# weightScale.net
KiCad netlist of a schematic drawn in EAGLE
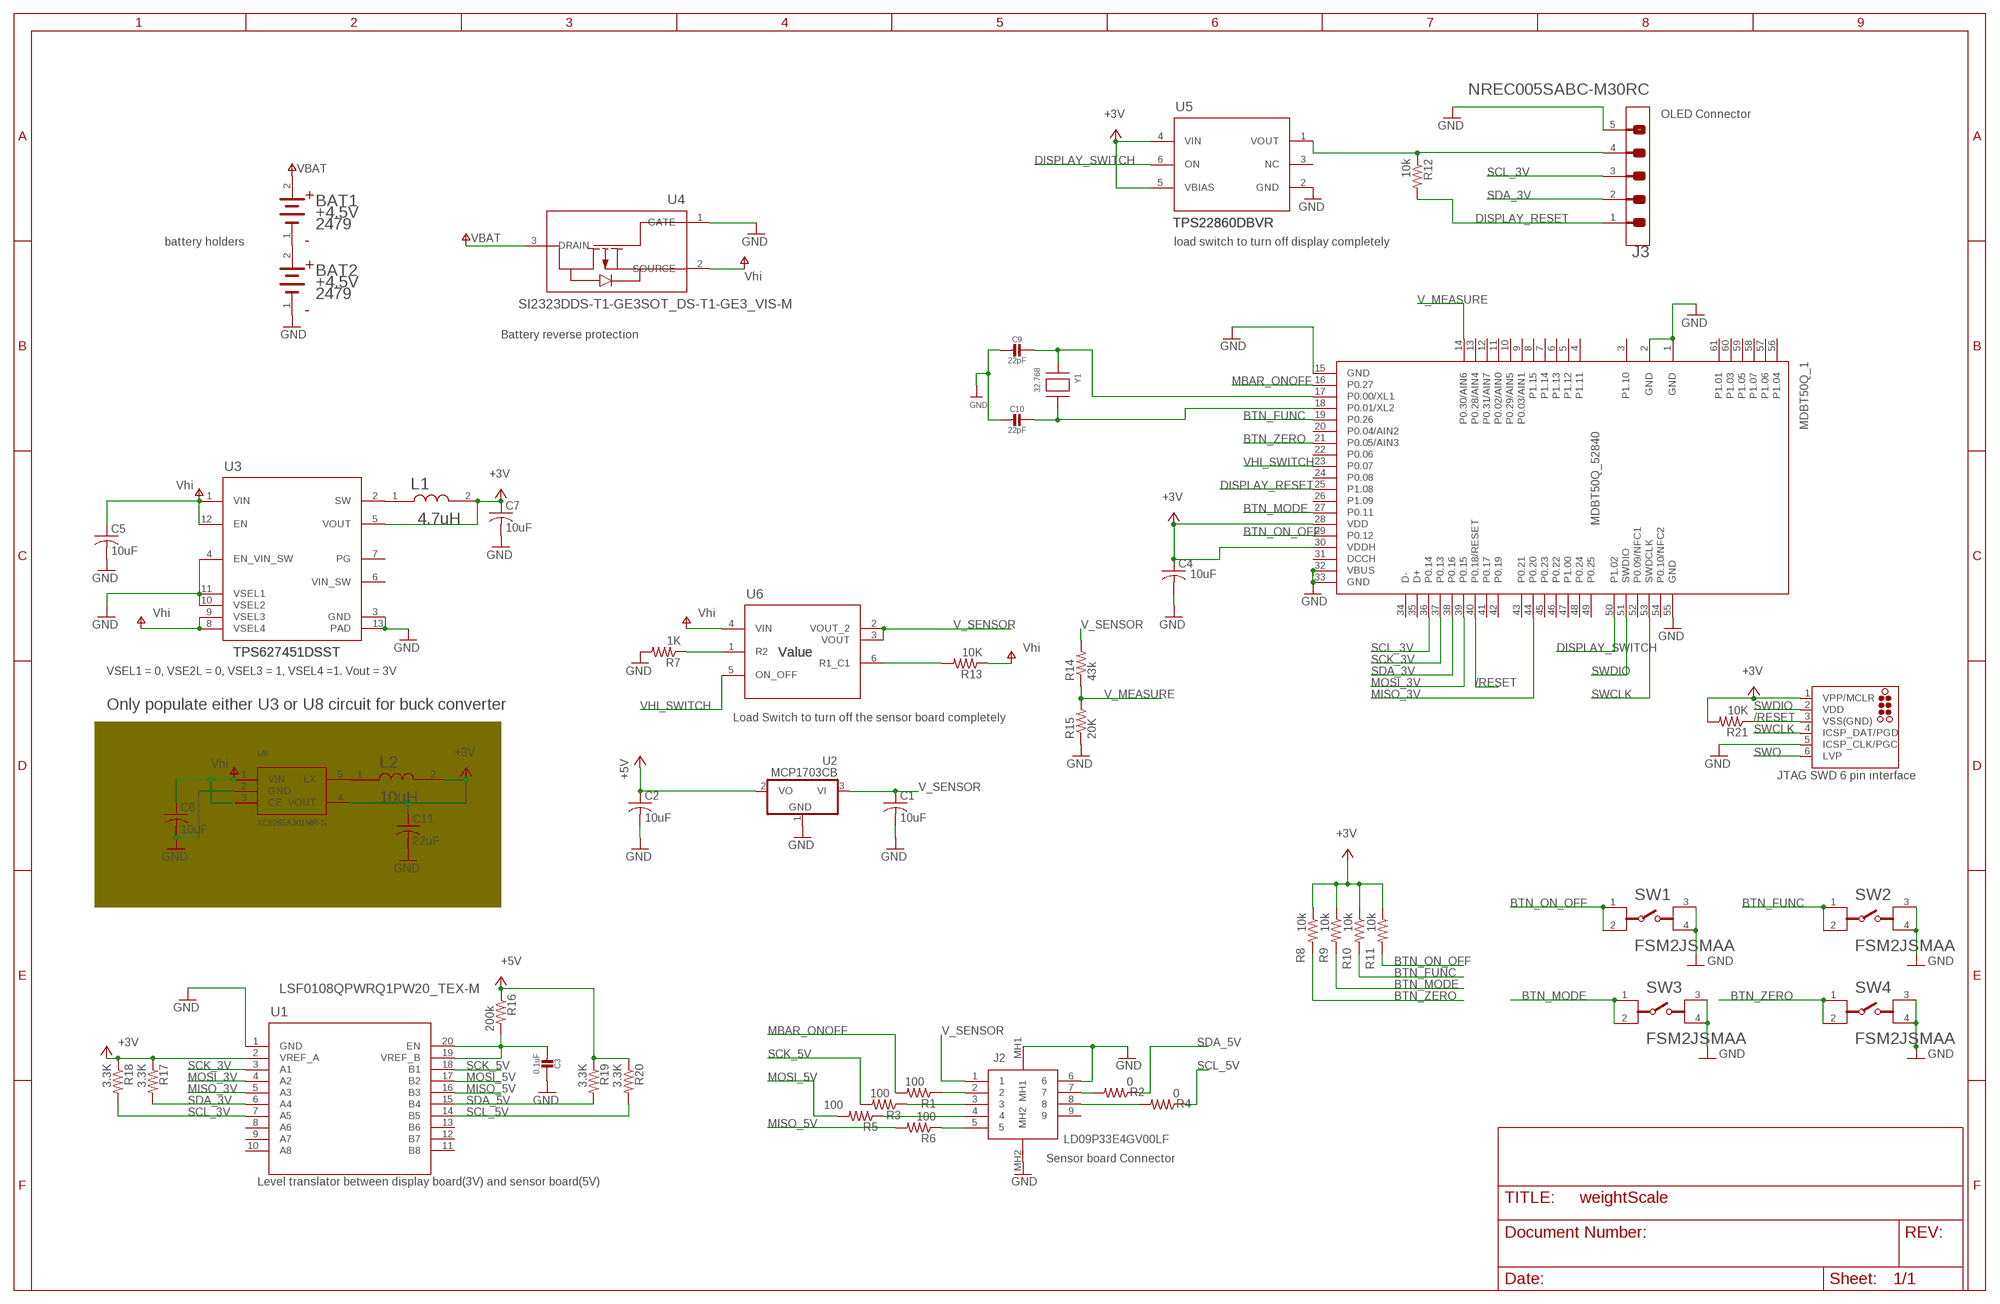
[diagram p0: schematic, sheet 1]

(export (version "E")
  (design (tool "Eeschema 10.0.6"))
  (components
    (comp (ref "BAT1")
      (value "KEYSTONE_2479KEYSTONE_2479_0_0")
      (footprint "eagle-import:KEYSTONE_2479_0")
      (fields
        (field (name "DIGIKEY_PART_NUMBER") "36-2479-ND")
        (field (name "MF") "Keystone")
        (field (name "MOUSER_PART_NUMBER") "534-2479")
      )
      (libsource (lib "eagle-import") (part "KEYSTONE_2479KEYSTONE_2479_0_0"))
    )
    (comp (ref "BAT2")
      (value "KEYSTONE_2479KEYSTONE_2479_0_0")
      (footprint "eagle-import:KEYSTONE_2479_0")
      (fields
        (field (name "DIGIKEY_PART_NUMBER") "36-2479-ND")
        (field (name "MF") "Keystone")
        (field (name "MOUSER_PART_NUMBER") "534-2479")
      )
      (libsource (lib "eagle-import") (part "KEYSTONE_2479KEYSTONE_2479_0_0"))
    )
    (comp (ref "C1")
      (value "10uF")
      (footprint "eagle-import:C0805")
      (libsource (lib "eagle-import") (part "C-USC0805"))
    )
    (comp (ref "C2")
      (value "10uF")
      (footprint "eagle-import:C0805")
      (libsource (lib "eagle-import") (part "C-USC0805"))
    )
    (comp (ref "C3")
      (value "0.1uF")
      (footprint "eagle-import:_0603MP")
      (libsource (lib "eagle-import") (part "CAP_CERAMIC_0603MP"))
    )
    (comp (ref "C4")
      (value "10uF")
      (footprint "eagle-import:C1206")
      (libsource (lib "eagle-import") (part "C-USC1206"))
    )
    (comp (ref "C5")
      (value "10uF")
      (footprint "eagle-import:C0805")
      (libsource (lib "eagle-import") (part "C-USC0805"))
    )
    (comp (ref "C6")
      (value "10uF")
      (footprint "eagle-import:C0603K")
      (libsource (lib "eagle-import") (part "C-USC0603K"))
    )
    (comp (ref "C7")
      (value "10uF")
      (footprint "eagle-import:C0805")
      (libsource (lib "eagle-import") (part "C-USC0805"))
    )
    (comp (ref "C9")
      (value "22pF")
      (footprint "eagle-import:_0603MP")
      (libsource (lib "eagle-import") (part "CAP_CERAMIC_0603MP"))
    )
    (comp (ref "C10")
      (value "22pF")
      (footprint "eagle-import:_0603MP")
      (libsource (lib "eagle-import") (part "CAP_CERAMIC_0603MP"))
    )
    (comp (ref "C11")
      (value "22uF")
      (footprint "eagle-import:C0603K")
      (libsource (lib "eagle-import") (part "C-USC0603K"))
    )
    (comp (ref "J2")
      (value "LD09P33E4GV00LF")
      (footprint "eagle-import:LD09P33E4GV00LF")
      (fields (field (name "MOUSER_PART_NUMBER") "649-LD09P33E4GV00LF"))
      (libsource (lib "eagle-import") (part "LD09P33E4GV00LF"))
    )
    (comp (ref "J3")
      (value "SULLINS_NREC005SABC-M30RCSULLINS_NREC005SABC-M30RC_0_0")
      (footprint "eagle-import:SULLINS_NREC005SABC-M30RC_0")
      (fields
        (field (name "DIGIKEY_PART_NUMBER") "CONN HEADER .100\" SNGL SMD 5POS")
        (field (name "MF") "Sullins")
        (field (name "MPN") "NREC005SABC-M30RC")
      )
      (libsource (lib "eagle-import") (part "SULLINS_NREC005SABC-M30RCSULLINS_NREC005SABC-M30RC_0_0"))
    )
    (comp (ref "J4")
      (value "TC2030-MCP-NL")
      (footprint "eagle-import:TC2030-MCP-NL")
      (libsource (lib "eagle-import") (part "TC2030-MCP-NL"))
    )
    (comp (ref "L1")
      (value "MURATA_DFE252010F-4R7M=P2MURATA_DFE252010F-4R7M=P2_0_0")
      (footprint "eagle-import:MURATA_DFE252010F-4R7M=P2_0")
      (fields
        (field (name "MF") "Murata")
        (field (name "MPN") "DFE252010F-4R7M=P2")
        (field (name "TOLERANCE") "0.2")
      )
      (libsource (lib "eagle-import") (part "MURATA_DFE252010F-4R7M=P2MURATA_DFE252010F-4R7M=P2_0_0"))
    )
    (comp (ref "L2")
      (value "MURATA_1239AS-H-100M=P2MURATA_1239AS-H-100M=P2_0_0")
      (footprint "eagle-import:MURATA_1239AS-H-100M=P2_0")
      (fields
        (field (name "DIGIKEY_PART_NUMBER") "490-10563-1-ND")
        (field (name "MF") "Murata")
        (field (name "MOUSER_PART_NUMBER") "81-1239AS-H-100MP2")
      )
      (libsource (lib "eagle-import") (part "MURATA_1239AS-H-100M=P2MURATA_1239AS-H-100M=P2_0_0"))
    )
    (comp (ref "MDBT50Q_1")
      (value "MDBT50Q_52840")
      (footprint "eagle-import:MDBT50Q")
      (libsource (lib "eagle-import") (part "MDBT50Q_52840"))
    )
    (comp (ref "R1")
      (value "100")
      (footprint "eagle-import:R0603")
      (libsource (lib "eagle-import") (part "R-US_R0603"))
    )
    (comp (ref "R2")
      (value "0")
      (footprint "eagle-import:R0603")
      (libsource (lib "eagle-import") (part "R-US_R0603"))
    )
    (comp (ref "R3")
      (value "100")
      (footprint "eagle-import:R0603")
      (libsource (lib "eagle-import") (part "R-US_R0603"))
    )
    (comp (ref "R4")
      (value "0")
      (footprint "eagle-import:R0603")
      (libsource (lib "eagle-import") (part "R-US_R0603"))
    )
    (comp (ref "R5")
      (value "100")
      (footprint "eagle-import:R0603")
      (libsource (lib "eagle-import") (part "R-US_R0603"))
    )
    (comp (ref "R6")
      (value "100")
      (footprint "eagle-import:R0603")
      (libsource (lib "eagle-import") (part "R-US_R0603"))
    )
    (comp (ref "R7")
      (value "1K")
      (footprint "eagle-import:R0603")
      (libsource (lib "eagle-import") (part "R-US_R0603"))
    )
    (comp (ref "R8")
      (value "10k")
      (footprint "eagle-import:R0603")
      (libsource (lib "eagle-import") (part "R-US_R0603"))
    )
    (comp (ref "R9")
      (value "10k")
      (footprint "eagle-import:R0603")
      (libsource (lib "eagle-import") (part "R-US_R0603"))
    )
    (comp (ref "R10")
      (value "10k")
      (footprint "eagle-import:R0603")
      (libsource (lib "eagle-import") (part "R-US_R0603"))
    )
    (comp (ref "R11")
      (value "10k")
      (footprint "eagle-import:R0603")
      (libsource (lib "eagle-import") (part "R-US_R0603"))
    )
    (comp (ref "R12")
      (value "10k")
      (footprint "eagle-import:R0603")
      (libsource (lib "eagle-import") (part "R-US_R0603"))
    )
    (comp (ref "R13")
      (value "10K")
      (footprint "eagle-import:R0603")
      (libsource (lib "eagle-import") (part "R-US_R0603"))
    )
    (comp (ref "R14")
      (value "43k")
      (footprint "eagle-import:R0603")
      (libsource (lib "eagle-import") (part "R-US_R0603"))
    )
    (comp (ref "R15")
      (value "20K")
      (footprint "eagle-import:R0603")
      (libsource (lib "eagle-import") (part "R-US_R0603"))
    )
    (comp (ref "R16")
      (value "200k")
      (footprint "eagle-import:R0603")
      (libsource (lib "eagle-import") (part "R-US_R0603"))
    )
    (comp (ref "R17")
      (value "3.3K")
      (footprint "eagle-import:R0603")
      (libsource (lib "eagle-import") (part "R-US_R0603"))
    )
    (comp (ref "R18")
      (value "3.3K")
      (footprint "eagle-import:R0603")
      (libsource (lib "eagle-import") (part "R-US_R0603"))
    )
    (comp (ref "R19")
      (value "3.3K")
      (footprint "eagle-import:R0603")
      (libsource (lib "eagle-import") (part "R-US_R0603"))
    )
    (comp (ref "R20")
      (value "3.3K")
      (footprint "eagle-import:R0603")
      (libsource (lib "eagle-import") (part "R-US_R0603"))
    )
    (comp (ref "R21")
      (value "10K")
      (footprint "eagle-import:R0603")
      (libsource (lib "eagle-import") (part "R-US_R0603"))
    )
    (comp (ref "SW1")
      (value "TE_CONNECTIVITY_FSM2JSMAATE_CONNECTIVITY_FSM2JSMAA_0_0")
      (footprint "eagle-import:TE_CONNECTIVITY_FSM2JSMAA_0")
      (fields
        (field (name "DIGIKEY_PART_NUMBER") "450-3355-ND")
        (field (name "MF") "TE Connectivity")
        (field (name "MOUSER_PART_NUMBER") "506-2-1437565-8")
      )
      (libsource (lib "eagle-import") (part "TE_CONNECTIVITY_FSM2JSMAATE_CONNECTIVITY_FSM2JSMAA_0_0"))
    )
    (comp (ref "SW2")
      (value "TE_CONNECTIVITY_FSM2JSMAATE_CONNECTIVITY_FSM2JSMAA_0_0")
      (footprint "eagle-import:TE_CONNECTIVITY_FSM2JSMAA_0")
      (fields
        (field (name "DIGIKEY_PART_NUMBER") "450-3355-ND")
        (field (name "MF") "TE Connectivity")
        (field (name "MOUSER_PART_NUMBER") "506-2-1437565-8")
      )
      (libsource (lib "eagle-import") (part "TE_CONNECTIVITY_FSM2JSMAATE_CONNECTIVITY_FSM2JSMAA_0_0"))
    )
    (comp (ref "SW3")
      (value "TE_CONNECTIVITY_FSM2JSMAATE_CONNECTIVITY_FSM2JSMAA_0_0")
      (footprint "eagle-import:TE_CONNECTIVITY_FSM2JSMAA_0")
      (fields
        (field (name "DIGIKEY_PART_NUMBER") "450-3355-ND")
        (field (name "MF") "TE Connectivity")
        (field (name "MOUSER_PART_NUMBER") "506-2-1437565-8")
      )
      (libsource (lib "eagle-import") (part "TE_CONNECTIVITY_FSM2JSMAATE_CONNECTIVITY_FSM2JSMAA_0_0"))
    )
    (comp (ref "SW4")
      (value "TE_CONNECTIVITY_FSM2JSMAATE_CONNECTIVITY_FSM2JSMAA_0_0")
      (footprint "eagle-import:TE_CONNECTIVITY_FSM2JSMAA_0")
      (fields
        (field (name "DIGIKEY_PART_NUMBER") "450-3355-ND")
        (field (name "MF") "TE Connectivity")
        (field (name "MOUSER_PART_NUMBER") "506-2-1437565-8")
      )
      (libsource (lib "eagle-import") (part "TE_CONNECTIVITY_FSM2JSMAATE_CONNECTIVITY_FSM2JSMAA_0_0"))
    )
    (comp (ref "U1")
      (value "LSF0108QPWRQ1PW20_TEX-M")
      (footprint "eagle-import:PW20_TEX-M")
      (fields
        (field (name "MANUFACTURER_PART_NUMBER") "LSF0108QPWRQ1")
        (field (name "COPYRIGHT") "Copyright (C) 2021 Ultra Librarian. All rights reserved.")
      )
      (libsource (lib "eagle-import") (part "LSF0108QPWRQ1PW20_TEX-M"))
    )
    (comp (ref "U2")
      (value "MCP1703CB")
      (footprint "eagle-import:SOT23")
      (libsource (lib "eagle-import") (part "MCP1703CB"))
    )
    (comp (ref "U3")
      (value "TPS627451DSST")
      (footprint "eagle-import:DSS0012A")
      (fields (field (name "COPYRIGHT") "Copyright (C) 2021 Ultra Librarian. All rights reserved."))
      (libsource (lib "eagle-import") (part "TPS627451DSST"))
    )
    (comp (ref "U4")
      (value "SI2323DDS-T1-GE3SOT_DS-T1-GE3_VIS-M")
      (footprint "eagle-import:SOT_DS-T1-GE3_VIS-M")
      (fields
        (field (name "MANUFACTURER_PART_NUMBER") "SI2323DDS-T1-GE3")
        (field (name "COPYRIGHT") "Copyright (C) 2021 Ultra Librarian. All rights reserved.")
      )
      (libsource (lib "eagle-import") (part "SI2323DDS-T1-GE3SOT_DS-T1-GE3_VIS-M"))
    )
    (comp (ref "U5")
      (value "TPS22860DBVR")
      (footprint "eagle-import:DBV0006A_N")
      (fields (field (name "COPYRIGHT") "Copyright (C) 2021 Ultra Librarian. All rights reserved."))
      (libsource (lib "eagle-import") (part "TPS22860DBVR"))
    )
    (comp (ref "U6")
      (value "Value")
      (footprint "eagle-import:DDC0006A_N")
      (fields (field (name "MANUFACTURER") "Texas Instruments") (field (name "PARTNUMBER") "TPS27081ADDCR"))
      (libsource (lib "eagle-import") (part "TPS27081ADDCR"))
    )
    (comp (ref "U8")
      (value "XC9265A301MR-G")
      (footprint "eagle-import:SOT-25")
      (libsource (lib "eagle-import") (part "XC9265A301MR-G"))
    )
    (comp (ref "Y1")
      (value "32.768")
      (footprint "eagle-import:XTAL3215")
      (libsource (lib "eagle-import") (part "XTAL-3.2X1.5"))
    )
  )
  (nets
    (net (code "1") (name "+3V") (class "Default")
      (node (ref "C11") (pin "1") (pinfunction "1_1") (pintype "passive"))
      (node (ref "C4") (pin "1") (pinfunction "1_1") (pintype "passive"))
      (node (ref "C7") (pin "1") (pinfunction "1_1") (pintype "passive"))
      (node (ref "J4") (pin "1") (pinfunction "VPP/MCLR_1") (pintype "passive"))
      (node (ref "L1") (pin "2") (pinfunction "2_2") (pintype "passive"))
      (node (ref "L2") (pin "2") (pinfunction "2_2") (pintype "passive"))
      (node (ref "MDBT50Q_1") (pin "28") (pinfunction "VDD_28") (pintype "bidirectional"))
      (node (ref "MDBT50Q_1") (pin "30") (pinfunction "VDDH_30") (pintype "bidirectional"))
      (node (ref "R10") (pin "1") (pinfunction "1_1") (pintype "passive"))
      (node (ref "R11") (pin "1") (pinfunction "1_1") (pintype "passive"))
      (node (ref "R17") (pin "1") (pinfunction "1_1") (pintype "passive"))
      (node (ref "R18") (pin "1") (pinfunction "1_1") (pintype "passive"))
      (node (ref "R21") (pin "2") (pinfunction "2_2") (pintype "passive"))
      (node (ref "R8") (pin "1") (pinfunction "1_1") (pintype "passive"))
      (node (ref "R9") (pin "1") (pinfunction "1_1") (pintype "passive"))
      (node (ref "U1") (pin "2") (pinfunction "VREF_A_2") (pintype "passive"))
      (node (ref "U3") (pin "5") (pinfunction "VOUT_5") (pintype "input"))
      (node (ref "U5") (pin "4") (pinfunction "VIN_4") (pintype "power_in"))
      (node (ref "U5") (pin "5") (pinfunction "VBIAS_5") (pintype "input"))
      (node (ref "U8") (pin "4") (pinfunction "VOUT_4") (pintype "bidirectional"))
    )
    (net (code "2") (name "+5V") (class "Default")
      (node (ref "C2") (pin "1") (pinfunction "1_1") (pintype "passive"))
      (node (ref "R16") (pin "1") (pinfunction "1_1") (pintype "passive"))
      (node (ref "R19") (pin "1") (pinfunction "1_1") (pintype "passive"))
      (node (ref "R20") (pin "1") (pinfunction "1_1") (pintype "passive"))
      (node (ref "U2") (pin "2") (pinfunction "VO_2") (pintype "passive"))
    )
    (net (code "3") (name "/BTN_FUNC") (class "Default")
      (node (ref "MDBT50Q_1") (pin "19") (pinfunction "P0.26_19") (pintype "bidirectional"))
      (node (ref "R10") (pin "2") (pinfunction "2_2") (pintype "passive"))
      (node (ref "SW2") (pin "1") (pinfunction "1_1") (pintype "passive"))
      (node (ref "SW2") (pin "2") (pinfunction "2_2") (pintype "passive"))
    )
    (net (code "4") (name "/BTN_MODE") (class "Default")
      (node (ref "MDBT50Q_1") (pin "27") (pinfunction "P0.11_27") (pintype "bidirectional"))
      (node (ref "R9") (pin "2") (pinfunction "2_2") (pintype "passive"))
      (node (ref "SW3") (pin "1") (pinfunction "1_1") (pintype "passive"))
      (node (ref "SW3") (pin "2") (pinfunction "2_2") (pintype "passive"))
    )
    (net (code "5") (name "/BTN_ON_OFF") (class "Default")
      (node (ref "MDBT50Q_1") (pin "29") (pinfunction "P0.12_29") (pintype "bidirectional"))
      (node (ref "R11") (pin "2") (pinfunction "2_2") (pintype "passive"))
      (node (ref "SW1") (pin "1") (pinfunction "1_1") (pintype "passive"))
      (node (ref "SW1") (pin "2") (pinfunction "2_2") (pintype "passive"))
    )
    (net (code "6") (name "/BTN_ZERO") (class "Default")
      (node (ref "MDBT50Q_1") (pin "21") (pinfunction "P0.05/AIN3_21") (pintype "bidirectional"))
      (node (ref "R8") (pin "2") (pinfunction "2_2") (pintype "passive"))
      (node (ref "SW4") (pin "1") (pinfunction "1_1") (pintype "passive"))
      (node (ref "SW4") (pin "2") (pinfunction "2_2") (pintype "passive"))
    )
    (net (code "7") (name "/DISPLAY_RESET") (class "Default")
      (node (ref "J3") (pin "1") (pinfunction "1_1") (pintype "bidirectional"))
      (node (ref "MDBT50Q_1") (pin "25") (pinfunction "P1.08_25") (pintype "bidirectional"))
      (node (ref "R12") (pin "2") (pinfunction "2_2") (pintype "passive"))
    )
    (net (code "8") (name "/DISPLAY_SWITCH") (class "Default")
      (node (ref "MDBT50Q_1") (pin "50") (pinfunction "P1.02_50") (pintype "bidirectional"))
      (node (ref "U5") (pin "6") (pinfunction "ON_6") (pintype "input"))
    )
    (net (code "9") (name "/MBAR_ONOFF") (class "Default")
      (node (ref "MDBT50Q_1") (pin "16") (pinfunction "P0.27_16") (pintype "bidirectional"))
      (node (ref "R1") (pin "2") (pinfunction "2_2") (pintype "passive"))
    )
    (net (code "10") (name "/MISO_3V") (class "Default")
      (node (ref "MDBT50Q_1") (pin "44") (pinfunction "P0.20_44") (pintype "bidirectional"))
      (node (ref "U1") (pin "5") (pinfunction "A3_5") (pintype "passive"))
    )
    (net (code "11") (name "/MISO_5V") (class "Default")
      (node (ref "R6") (pin "2") (pinfunction "2_2") (pintype "passive"))
      (node (ref "U1") (pin "16") (pinfunction "B3_16") (pintype "passive"))
    )
    (net (code "12") (name "/MOSI_3V") (class "Default")
      (node (ref "MDBT50Q_1") (pin "39") (pinfunction "P0.15_39") (pintype "bidirectional"))
      (node (ref "U1") (pin "4") (pinfunction "A2_4") (pintype "passive"))
    )
    (net (code "13") (name "/MOSI_5V") (class "Default")
      (node (ref "R5") (pin "2") (pinfunction "2_2") (pintype "passive"))
      (node (ref "U1") (pin "17") (pinfunction "B2_17") (pintype "passive"))
    )
    (net (code "14") (name "/SCK_3V") (class "Default")
      (node (ref "MDBT50Q_1") (pin "37") (pinfunction "P0.13_37") (pintype "bidirectional"))
      (node (ref "U1") (pin "3") (pinfunction "A1_3") (pintype "passive"))
    )
    (net (code "15") (name "/SCK_5V") (class "Default")
      (node (ref "R3") (pin "2") (pinfunction "2_2") (pintype "passive"))
      (node (ref "U1") (pin "18") (pinfunction "B1_18") (pintype "passive"))
    )
    (net (code "16") (name "/SCL_3V") (class "Default")
      (node (ref "J3") (pin "3") (pinfunction "3_3") (pintype "bidirectional"))
      (node (ref "MDBT50Q_1") (pin "36") (pinfunction "P0.14_36") (pintype "bidirectional"))
      (node (ref "R18") (pin "2") (pinfunction "2_2") (pintype "passive"))
      (node (ref "U1") (pin "7") (pinfunction "A5_7") (pintype "passive"))
    )
    (net (code "17") (name "/SCL_5V") (class "Default")
      (node (ref "R20") (pin "2") (pinfunction "2_2") (pintype "passive"))
      (node (ref "R4") (pin "1") (pinfunction "1_1") (pintype "passive"))
      (node (ref "U1") (pin "14") (pinfunction "B5_14") (pintype "passive"))
    )
    (net (code "18") (name "/SDA_3V") (class "Default")
      (node (ref "J3") (pin "2") (pinfunction "2_2") (pintype "bidirectional"))
      (node (ref "MDBT50Q_1") (pin "38") (pinfunction "P0.16_38") (pintype "bidirectional"))
      (node (ref "R17") (pin "2") (pinfunction "2_2") (pintype "passive"))
      (node (ref "U1") (pin "6") (pinfunction "A4_6") (pintype "passive"))
    )
    (net (code "19") (name "/SDA_5V") (class "Default")
      (node (ref "R19") (pin "2") (pinfunction "2_2") (pintype "passive"))
      (node (ref "R2") (pin "1") (pinfunction "1_1") (pintype "passive"))
      (node (ref "U1") (pin "15") (pinfunction "B4_15") (pintype "passive"))
    )
    (net (code "20") (name "/SWCLK") (class "Default")
      (node (ref "J4") (pin "4") (pinfunction "ICSP_DAT/PGD_4") (pintype "bidirectional"))
      (node (ref "MDBT50Q_1") (pin "53") (pinfunction "SWDCLK_53") (pintype "bidirectional"))
    )
    (net (code "21") (name "/SWDIO") (class "Default")
      (node (ref "J4") (pin "2") (pinfunction "VDD_2") (pintype "power_in"))
      (node (ref "MDBT50Q_1") (pin "51") (pinfunction "SWDIO_51") (pintype "bidirectional"))
    )
    (net (code "22") (name "/SWO") (class "Default")
      (node (ref "J4") (pin "6") (pinfunction "LVP_6") (pintype "bidirectional"))
    )
    (net (code "23") (name "/VHI_SWITCH") (class "Default")
      (node (ref "MDBT50Q_1") (pin "23") (pinfunction "P0.07_23") (pintype "bidirectional"))
      (node (ref "U6") (pin "5") (pinfunction "ON_OFF_5") (pintype "input"))
    )
    (net (code "24") (name "/VIN_SW") (class "Default")
      (node (ref "U3") (pin "6") (pinfunction "VIN_SW_6") (pintype "power_in"))
    )
    (net (code "25") (name "/V_MEASURE") (class "Default")
      (node (ref "MDBT50Q_1") (pin "14") (pinfunction "P0.30/AIN6_14") (pintype "bidirectional"))
      (node (ref "R14") (pin "1") (pinfunction "1_1") (pintype "passive"))
      (node (ref "R15") (pin "2") (pinfunction "2_2") (pintype "passive"))
    )
    (net (code "26") (name "/V_SENSOR") (class "Default")
      (node (ref "C1") (pin "1") (pinfunction "1_1") (pintype "passive"))
      (node (ref "J2") (pin "1") (pinfunction "1_1") (pintype "bidirectional"))
      (node (ref "R14") (pin "2") (pinfunction "2_2") (pintype "passive"))
      (node (ref "U2") (pin "3") (pinfunction "VI_3") (pintype "input"))
      (node (ref "U6") (pin "2") (pinfunction "VOUT_2_2") (pintype "power_in"))
      (node (ref "U6") (pin "3") (pinfunction "VOUT_3") (pintype "power_in"))
    )
    (net (code "27") (name "/{slash}RESET") (class "Default")
      (node (ref "J4") (pin "3") (pinfunction "VSS(GND)_3") (pintype "power_in"))
      (node (ref "MDBT50Q_1") (pin "40") (pinfunction "P0.18/RESET_40") (pintype "bidirectional"))
      (node (ref "R21") (pin "1") (pinfunction "1_1") (pintype "passive"))
    )
    (net (code "28") (name "GND") (class "Default")
      (node (ref "BAT2") (pin "1") (pinfunction "CATHODE_1") (pintype "bidirectional"))
      (node (ref "C1") (pin "2") (pinfunction "2_2") (pintype "passive"))
      (node (ref "C10") (pin "2") (pinfunction "2_2") (pintype "passive"))
      (node (ref "C11") (pin "2") (pinfunction "2_2") (pintype "passive"))
      (node (ref "C2") (pin "2") (pinfunction "2_2") (pintype "passive"))
      (node (ref "C3") (pin "1") (pinfunction "1_1") (pintype "passive"))
      (node (ref "C4") (pin "2") (pinfunction "2_2") (pintype "passive"))
      (node (ref "C5") (pin "2") (pinfunction "2_2") (pintype "passive"))
      (node (ref "C6") (pin "2") (pinfunction "2_2") (pintype "passive"))
      (node (ref "C7") (pin "2") (pinfunction "2_2") (pintype "passive"))
      (node (ref "C9") (pin "2") (pinfunction "2_2") (pintype "passive"))
      (node (ref "J2") (pin "6") (pinfunction "6_6") (pintype "bidirectional"))
      (node (ref "J2") (pin "MH1") (pinfunction "MH1_MH1") (pintype "bidirectional"))
      (node (ref "J2") (pin "MH2") (pinfunction "MH2_MH2") (pintype "bidirectional"))
      (node (ref "J3") (pin "5") (pinfunction "5_5") (pintype "bidirectional"))
      (node (ref "J4") (pin "5") (pinfunction "ICSP_CLK/PGC_5") (pintype "output"))
      (node (ref "MDBT50Q_1") (pin "1") (pinfunction "GND_1") (pintype "bidirectional"))
      (node (ref "MDBT50Q_1") (pin "15") (pinfunction "GND_15") (pintype "bidirectional"))
      (node (ref "MDBT50Q_1") (pin "2") (pinfunction "GND_2") (pintype "bidirectional"))
      (node (ref "MDBT50Q_1") (pin "32") (pinfunction "VBUS_32") (pintype "bidirectional"))
      (node (ref "MDBT50Q_1") (pin "33") (pinfunction "GND_33") (pintype "bidirectional"))
      (node (ref "MDBT50Q_1") (pin "55") (pinfunction "GND_55") (pintype "bidirectional"))
      (node (ref "R15") (pin "1") (pinfunction "1_1") (pintype "passive"))
      (node (ref "R7") (pin "2") (pinfunction "2_2") (pintype "passive"))
      (node (ref "SW1") (pin "3") (pinfunction "3_3") (pintype "passive"))
      (node (ref "SW1") (pin "4") (pinfunction "4_4") (pintype "passive"))
      (node (ref "SW2") (pin "3") (pinfunction "3_3") (pintype "passive"))
      (node (ref "SW2") (pin "4") (pinfunction "4_4") (pintype "passive"))
      (node (ref "SW3") (pin "3") (pinfunction "3_3") (pintype "passive"))
      (node (ref "SW3") (pin "4") (pinfunction "4_4") (pintype "passive"))
      (node (ref "SW4") (pin "3") (pinfunction "3_3") (pintype "passive"))
      (node (ref "SW4") (pin "4") (pinfunction "4_4") (pintype "passive"))
      (node (ref "U1") (pin "1") (pinfunction "GND_1") (pintype "power_in"))
      (node (ref "U2") (pin "1") (pinfunction "GND_1") (pintype "passive"))
      (node (ref "U3") (pin "10") (pinfunction "VSEL2_10") (pintype "input"))
      (node (ref "U3") (pin "11") (pinfunction "VSEL1_11") (pintype "input"))
      (node (ref "U3") (pin "13") (pinfunction "PAD_13") (pintype "passive"))
      (node (ref "U3") (pin "3") (pinfunction "GND_3") (pintype "power_in"))
      (node (ref "U3") (pin "4") (pinfunction "EN_VIN_SW_4") (pintype "input"))
      (node (ref "U4") (pin "1") (pinfunction "GATE_1") (pintype "passive"))
      (node (ref "U5") (pin "2") (pinfunction "GND_2") (pintype "power_in"))
      (node (ref "U8") (pin "2") (pinfunction "GND_2") (pintype "bidirectional"))
    )
    (net (code "29") (name "Net-(BAT1-CATHODE)") (class "Default")
      (node (ref "BAT1") (pin "1") (pinfunction "CATHODE_1") (pintype "bidirectional"))
      (node (ref "BAT2") (pin "2") (pinfunction "ANODE_2") (pintype "bidirectional"))
    )
    (net (code "30") (name "Net-(J2-Pad2)") (class "Default")
      (node (ref "J2") (pin "2") (pinfunction "2_2") (pintype "bidirectional"))
      (node (ref "R1") (pin "1") (pinfunction "1_1") (pintype "passive"))
    )
    (net (code "31") (name "Net-(J2-Pad3)") (class "Default")
      (node (ref "J2") (pin "3") (pinfunction "3_3") (pintype "bidirectional"))
      (node (ref "R3") (pin "1") (pinfunction "1_1") (pintype "passive"))
    )
    (net (code "32") (name "Net-(J2-Pad4)") (class "Default")
      (node (ref "J2") (pin "4") (pinfunction "4_4") (pintype "bidirectional"))
      (node (ref "R5") (pin "1") (pinfunction "1_1") (pintype "passive"))
    )
    (net (code "33") (name "Net-(J2-Pad5)") (class "Default")
      (node (ref "J2") (pin "5") (pinfunction "5_5") (pintype "bidirectional"))
      (node (ref "R6") (pin "1") (pinfunction "1_1") (pintype "passive"))
    )
    (net (code "34") (name "Net-(J2-Pad7)") (class "Default")
      (node (ref "J2") (pin "7") (pinfunction "7_7") (pintype "bidirectional"))
      (node (ref "R2") (pin "2") (pinfunction "2_2") (pintype "passive"))
    )
    (net (code "35") (name "Net-(J2-Pad8)") (class "Default")
      (node (ref "J2") (pin "8") (pinfunction "8_8") (pintype "bidirectional"))
      (node (ref "R4") (pin "2") (pinfunction "2_2") (pintype "passive"))
    )
    (net (code "36") (name "Net-(MDBT50Q_1-P0.00{slash}XL1)") (class "Default")
      (node (ref "C9") (pin "1") (pinfunction "1_1") (pintype "passive"))
      (node (ref "MDBT50Q_1") (pin "17") (pinfunction "P0.00/XL1_17") (pintype "bidirectional"))
      (node (ref "Y1") (pin "P$1") (pinfunction "P$1_P$1") (pintype "bidirectional"))
    )
    (net (code "37") (name "Net-(MDBT50Q_1-P0.01{slash}XL2)") (class "Default")
      (node (ref "C10") (pin "1") (pinfunction "1_1") (pintype "passive"))
      (node (ref "MDBT50Q_1") (pin "18") (pinfunction "P0.01/XL2_18") (pintype "bidirectional"))
      (node (ref "Y1") (pin "P$2") (pinfunction "P$2_P$2") (pintype "bidirectional"))
    )
    (net (code "38") (name "Net-(U1-EN)") (class "Default")
      (node (ref "C3") (pin "2") (pinfunction "2_2") (pintype "passive"))
      (node (ref "R16") (pin "2") (pinfunction "2_2") (pintype "passive"))
      (node (ref "U1") (pin "19") (pinfunction "VREF_B_19") (pintype "passive"))
      (node (ref "U1") (pin "20") (pinfunction "EN_20") (pintype "passive"))
    )
    (net (code "39") (name "Net-(U3-SW)") (class "Default")
      (node (ref "L1") (pin "1") (pinfunction "1_1") (pintype "passive"))
      (node (ref "U3") (pin "2") (pinfunction "SW_2") (pintype "power_in"))
    )
    (net (code "40") (name "Net-(U5-VOUT)") (class "Default")
      (node (ref "J3") (pin "4") (pinfunction "4_4") (pintype "bidirectional"))
      (node (ref "R12") (pin "1") (pinfunction "1_1") (pintype "passive"))
      (node (ref "U5") (pin "1") (pinfunction "VOUT_1") (pintype "power_in"))
    )
    (net (code "41") (name "Net-(U6-R1_C1)") (class "Default")
      (node (ref "R13") (pin "2") (pinfunction "2_2") (pintype "passive"))
      (node (ref "U6") (pin "6") (pinfunction "R1_C1_6") (pintype "input"))
    )
    (net (code "42") (name "Net-(U6-R2)") (class "Default")
      (node (ref "R7") (pin "1") (pinfunction "1_1") (pintype "passive"))
      (node (ref "U6") (pin "1") (pinfunction "R2_1") (pintype "input"))
    )
    (net (code "43") (name "Net-(U8-LX)") (class "Default")
      (node (ref "L2") (pin "1") (pinfunction "1_1") (pintype "passive"))
      (node (ref "U8") (pin "5") (pinfunction "LX_5") (pintype "bidirectional"))
    )
    (net (code "44") (name "VBAT") (class "Default")
      (node (ref "BAT1") (pin "2") (pinfunction "ANODE_2") (pintype "bidirectional"))
      (node (ref "C5") (pin "1") (pinfunction "1_1") (pintype "passive"))
      (node (ref "C6") (pin "1") (pinfunction "1_1") (pintype "passive"))
      (node (ref "R13") (pin "1") (pinfunction "1_1") (pintype "passive"))
      (node (ref "U3") (pin "1") (pinfunction "VIN_1") (pintype "power_in"))
      (node (ref "U3") (pin "12") (pinfunction "EN_12") (pintype "input"))
      (node (ref "U3") (pin "8") (pinfunction "VSEL4_8") (pintype "input"))
      (node (ref "U3") (pin "9") (pinfunction "VSEL3_9") (pintype "input"))
      (node (ref "U4") (pin "2") (pinfunction "SOURCE_2") (pintype "passive"))
      (node (ref "U4") (pin "3") (pinfunction "DRAIN_3") (pintype "passive"))
      (node (ref "U6") (pin "4") (pinfunction "VIN_4") (pintype "power_in"))
      (node (ref "U8") (pin "1") (pinfunction "VIN_1") (pintype "bidirectional"))
      (node (ref "U8") (pin "3") (pinfunction "CE_3") (pintype "bidirectional"))
    )
    (net (code "45") (name "unconnected-(J2-Pad9)") (class "Default")
      (node (ref "J2") (pin "9") (pinfunction "9_9") (pintype "bidirectional"))
    )
    (net (code "46") (name "unconnected-(MDBT50Q_1-D+-Pad35)") (class "Default")
      (node (ref "MDBT50Q_1") (pin "35") (pinfunction "D+_35") (pintype "bidirectional"))
    )
    (net (code "47") (name "unconnected-(MDBT50Q_1-D--Pad34)") (class "Default")
      (node (ref "MDBT50Q_1") (pin "34") (pinfunction "D-_34") (pintype "bidirectional"))
    )
    (net (code "48") (name "unconnected-(MDBT50Q_1-DCCH-Pad31)") (class "Default")
      (node (ref "MDBT50Q_1") (pin "31") (pinfunction "DCCH_31") (pintype "bidirectional"))
    )
    (net (code "49") (name "unconnected-(MDBT50Q_1-P0.02{slash}AIN0-Pad11)") (class "Default")
      (node (ref "MDBT50Q_1") (pin "11") (pinfunction "P0.02/AIN0_11") (pintype "bidirectional"))
    )
    (net (code "50") (name "unconnected-(MDBT50Q_1-P0.03{slash}AIN1-Pad9)") (class "Default")
      (node (ref "MDBT50Q_1") (pin "9") (pinfunction "P0.03/AIN1_9") (pintype "bidirectional"))
    )
    (net (code "51") (name "unconnected-(MDBT50Q_1-P0.04{slash}AIN2-Pad20)") (class "Default")
      (node (ref "MDBT50Q_1") (pin "20") (pinfunction "P0.04/AIN2_20") (pintype "bidirectional"))
    )
    (net (code "52") (name "unconnected-(MDBT50Q_1-P0.06-Pad22)") (class "Default")
      (node (ref "MDBT50Q_1") (pin "22") (pinfunction "P0.06_22") (pintype "bidirectional"))
    )
    (net (code "53") (name "unconnected-(MDBT50Q_1-P0.08-Pad24)") (class "Default")
      (node (ref "MDBT50Q_1") (pin "24") (pinfunction "P0.08_24") (pintype "bidirectional"))
    )
    (net (code "54") (name "unconnected-(MDBT50Q_1-P0.09{slash}NFC1-Pad52)") (class "Default")
      (node (ref "MDBT50Q_1") (pin "52") (pinfunction "P0.09/NFC1_52") (pintype "bidirectional"))
    )
    (net (code "55") (name "unconnected-(MDBT50Q_1-P0.10{slash}NFC2-Pad54)") (class "Default")
      (node (ref "MDBT50Q_1") (pin "54") (pinfunction "P0.10/NFC2_54") (pintype "bidirectional"))
    )
    (net (code "56") (name "unconnected-(MDBT50Q_1-P0.17-Pad41)") (class "Default")
      (node (ref "MDBT50Q_1") (pin "41") (pinfunction "P0.17_41") (pintype "bidirectional"))
    )
    (net (code "57") (name "unconnected-(MDBT50Q_1-P0.19-Pad42)") (class "Default")
      (node (ref "MDBT50Q_1") (pin "42") (pinfunction "P0.19_42") (pintype "bidirectional"))
    )
    (net (code "58") (name "unconnected-(MDBT50Q_1-P0.21-Pad43)") (class "Default")
      (node (ref "MDBT50Q_1") (pin "43") (pinfunction "P0.21_43") (pintype "bidirectional"))
    )
    (net (code "59") (name "unconnected-(MDBT50Q_1-P0.22-Pad46)") (class "Default")
      (node (ref "MDBT50Q_1") (pin "46") (pinfunction "P0.22_46") (pintype "bidirectional"))
    )
    (net (code "60") (name "unconnected-(MDBT50Q_1-P0.23-Pad45)") (class "Default")
      (node (ref "MDBT50Q_1") (pin "45") (pinfunction "P0.23_45") (pintype "bidirectional"))
    )
    (net (code "61") (name "unconnected-(MDBT50Q_1-P0.24-Pad48)") (class "Default")
      (node (ref "MDBT50Q_1") (pin "48") (pinfunction "P0.24_48") (pintype "bidirectional"))
    )
    (net (code "62") (name "unconnected-(MDBT50Q_1-P0.25-Pad49)") (class "Default")
      (node (ref "MDBT50Q_1") (pin "49") (pinfunction "P0.25_49") (pintype "bidirectional"))
    )
    (net (code "63") (name "unconnected-(MDBT50Q_1-P0.28{slash}AIN4-Pad13)") (class "Default")
      (node (ref "MDBT50Q_1") (pin "13") (pinfunction "P0.28/AIN4_13") (pintype "bidirectional"))
    )
    (net (code "64") (name "unconnected-(MDBT50Q_1-P0.29{slash}AIN5-Pad10)") (class "Default")
      (node (ref "MDBT50Q_1") (pin "10") (pinfunction "P0.29/AIN5_10") (pintype "bidirectional"))
    )
    (net (code "65") (name "unconnected-(MDBT50Q_1-P0.31{slash}AIN7-Pad12)") (class "Default")
      (node (ref "MDBT50Q_1") (pin "12") (pinfunction "P0.31/AIN7_12") (pintype "bidirectional"))
    )
    (net (code "66") (name "unconnected-(MDBT50Q_1-P1.00-Pad47)") (class "Default")
      (node (ref "MDBT50Q_1") (pin "47") (pinfunction "P1.00_47") (pintype "bidirectional"))
    )
    (net (code "67") (name "unconnected-(MDBT50Q_1-P1.01-Pad61)") (class "Default")
      (node (ref "MDBT50Q_1") (pin "61") (pinfunction "P1.01_61") (pintype "bidirectional"))
    )
    (net (code "68") (name "unconnected-(MDBT50Q_1-P1.03-Pad60)") (class "Default")
      (node (ref "MDBT50Q_1") (pin "60") (pinfunction "P1.03_60") (pintype "bidirectional"))
    )
    (net (code "69") (name "unconnected-(MDBT50Q_1-P1.04-Pad56)") (class "Default")
      (node (ref "MDBT50Q_1") (pin "56") (pinfunction "P1.04_56") (pintype "bidirectional"))
    )
    (net (code "70") (name "unconnected-(MDBT50Q_1-P1.05-Pad59)") (class "Default")
      (node (ref "MDBT50Q_1") (pin "59") (pinfunction "P1.05_59") (pintype "bidirectional"))
    )
    (net (code "71") (name "unconnected-(MDBT50Q_1-P1.06-Pad57)") (class "Default")
      (node (ref "MDBT50Q_1") (pin "57") (pinfunction "P1.06_57") (pintype "bidirectional"))
    )
    (net (code "72") (name "unconnected-(MDBT50Q_1-P1.07-Pad58)") (class "Default")
      (node (ref "MDBT50Q_1") (pin "58") (pinfunction "P1.07_58") (pintype "bidirectional"))
    )
    (net (code "73") (name "unconnected-(MDBT50Q_1-P1.09-Pad26)") (class "Default")
      (node (ref "MDBT50Q_1") (pin "26") (pinfunction "P1.09_26") (pintype "bidirectional"))
    )
    (net (code "74") (name "unconnected-(MDBT50Q_1-P1.10-Pad3)") (class "Default")
      (node (ref "MDBT50Q_1") (pin "3") (pinfunction "P1.10_3") (pintype "bidirectional"))
    )
    (net (code "75") (name "unconnected-(MDBT50Q_1-P1.11-Pad4)") (class "Default")
      (node (ref "MDBT50Q_1") (pin "4") (pinfunction "P1.11_4") (pintype "bidirectional"))
    )
    (net (code "76") (name "unconnected-(MDBT50Q_1-P1.12-Pad5)") (class "Default")
      (node (ref "MDBT50Q_1") (pin "5") (pinfunction "P1.12_5") (pintype "bidirectional"))
    )
    (net (code "77") (name "unconnected-(MDBT50Q_1-P1.13-Pad6)") (class "Default")
      (node (ref "MDBT50Q_1") (pin "6") (pinfunction "P1.13_6") (pintype "bidirectional"))
    )
    (net (code "78") (name "unconnected-(MDBT50Q_1-P1.14-Pad7)") (class "Default")
      (node (ref "MDBT50Q_1") (pin "7") (pinfunction "P1.14_7") (pintype "bidirectional"))
    )
    (net (code "79") (name "unconnected-(MDBT50Q_1-P1.15-Pad8)") (class "Default")
      (node (ref "MDBT50Q_1") (pin "8") (pinfunction "P1.15_8") (pintype "bidirectional"))
    )
    (net (code "80") (name "unconnected-(U1-A6-Pad8)") (class "Default")
      (node (ref "U1") (pin "8") (pinfunction "A6_8") (pintype "passive"))
    )
    (net (code "81") (name "unconnected-(U1-A7-Pad9)") (class "Default")
      (node (ref "U1") (pin "9") (pinfunction "A7_9") (pintype "passive"))
    )
    (net (code "82") (name "unconnected-(U1-A8-Pad10)") (class "Default")
      (node (ref "U1") (pin "10") (pinfunction "A8_10") (pintype "passive"))
    )
    (net (code "83") (name "unconnected-(U1-B6-Pad13)") (class "Default")
      (node (ref "U1") (pin "13") (pinfunction "B6_13") (pintype "passive"))
    )
    (net (code "84") (name "unconnected-(U1-B7-Pad12)") (class "Default")
      (node (ref "U1") (pin "12") (pinfunction "B7_12") (pintype "passive"))
    )
    (net (code "85") (name "unconnected-(U1-B8-Pad11)") (class "Default")
      (node (ref "U1") (pin "11") (pinfunction "B8_11") (pintype "passive"))
    )
    (net (code "86") (name "unconnected-(U3-PG-Pad7)") (class "Default")
      (node (ref "U3") (pin "7") (pinfunction "PG_7") (pintype "output"))
    )
    (net (code "87") (name "unconnected-(U5-NC-Pad3)") (class "Default")
      (node (ref "U5") (pin "3") (pinfunction "NC_3") (pintype "passive"))
    )
  )
)
